# fpc.net
KiCad netlist of a schematic drawn in Altium Designer
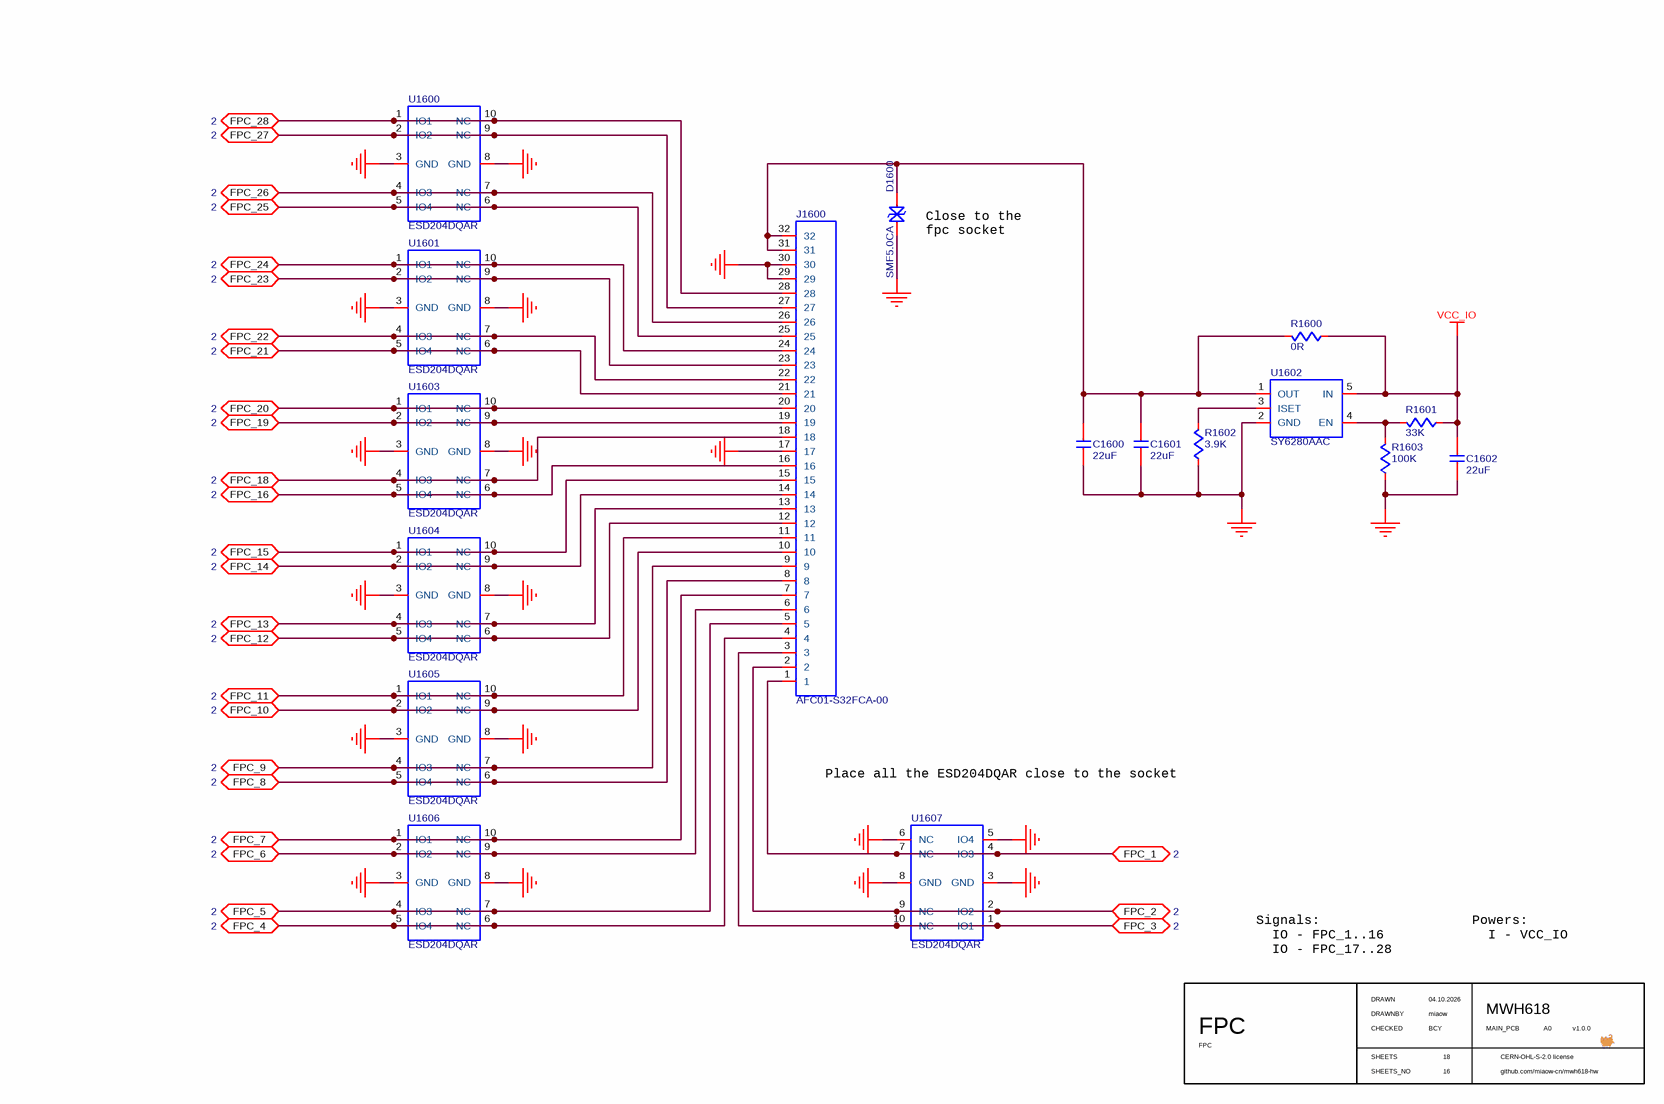
[diagram p0: fpc.schdoc]

(export (version "E")
  (design (tool "Eeschema 10.0.6"))
  (components
    (comp (ref "C1600")
      (value "22uF")
      (footprint "mw:C0603")
      (fields (field (name "VOLTAGE") "10V") (field (name "Comment") "C-NOMO"))
      (libsource (lib "mw") (part "C-NOMO"))
    )
    (comp (ref "C1601")
      (value "22uF")
      (footprint "mw:C0603")
      (fields (field (name "VOLTAGE") "10V") (field (name "Comment") "C-NOMO"))
      (libsource (lib "mw") (part "C-NOMO"))
    )
    (comp (ref "C1602")
      (value "22uF")
      (footprint "mw:C0603")
      (fields (field (name "VOLTAGE") "10V") (field (name "Comment") "C-NOMO"))
      (libsource (lib "mw") (part "C-NOMO"))
    )
    (comp (ref "D1600")
      (value "SMF5.0CA")
      (footprint "mw:SMF5.0CA")
      (description "TVS/ESD")
      (libsource (lib "mw") (part "SMF5.0CA"))
    )
    (comp (ref "J1600")
      (value "AFC01-S32FCA-00")
      (footprint "mw:AFC01-S32FCA-00")
      (description "FPC - flip, 32p, 0.5mm")
      (libsource (lib "mw") (part "AFC01-S32FCA-00"))
    )
    (comp (ref "R1600")
      (value "0R")
      (footprint "mw:R1206")
      (fields (field (name "Comment") "R"))
      (libsource (lib "mw") (part "R"))
    )
    (comp (ref "R1601")
      (value "33K")
      (footprint "mw:R0402")
      (fields (field (name "Comment") "R"))
      (libsource (lib "mw") (part "R"))
    )
    (comp (ref "R1602")
      (value "3.9K")
      (footprint "mw:R0402")
      (fields (field (name "Comment") "R"))
      (libsource (lib "mw") (part "R"))
    )
    (comp (ref "R1603")
      (value "100K")
      (footprint "mw:R0402")
      (fields (field (name "Comment") "R"))
      (libsource (lib "mw") (part "R"))
    )
    (comp (ref "U1600")
      (value "ESD204DQAR")
      (footprint "mw:ESD204DQAR")
      (description "TVS/ESD - 4 ch, 3.6V, 5V, 0.55pF@1MHz, 30KV")
      (libsource (lib "mw") (part "ESD204DQAR"))
    )
    (comp (ref "U1601")
      (value "ESD204DQAR")
      (footprint "mw:ESD204DQAR")
      (description "TVS/ESD - 4 ch, 3.6V, 5V, 0.55pF@1MHz, 30KV")
      (libsource (lib "mw") (part "ESD204DQAR"))
    )
    (comp (ref "U1602")
      (value "SY6280AAC")
      (footprint "mw:SY6280AAC")
      (description "PWR SWITCH")
      (libsource (lib "mw") (part "SY6280AAC"))
    )
    (comp (ref "U1603")
      (value "ESD204DQAR")
      (footprint "mw:ESD204DQAR")
      (description "TVS/ESD - 4 ch, 3.6V, 5V, 0.55pF@1MHz, 30KV")
      (libsource (lib "mw") (part "ESD204DQAR"))
    )
    (comp (ref "U1604")
      (value "ESD204DQAR")
      (footprint "mw:ESD204DQAR")
      (description "TVS/ESD - 4 ch, 3.6V, 5V, 0.55pF@1MHz, 30KV")
      (libsource (lib "mw") (part "ESD204DQAR"))
    )
    (comp (ref "U1605")
      (value "ESD204DQAR")
      (footprint "mw:ESD204DQAR")
      (description "TVS/ESD - 4 ch, 3.6V, 5V, 0.55pF@1MHz, 30KV")
      (libsource (lib "mw") (part "ESD204DQAR"))
    )
    (comp (ref "U1606")
      (value "ESD204DQAR")
      (footprint "mw:ESD204DQAR")
      (description "TVS/ESD - 4 ch, 3.6V, 5V, 0.55pF@1MHz, 30KV")
      (libsource (lib "mw") (part "ESD204DQAR"))
    )
    (comp (ref "U1607")
      (value "ESD204DQAR")
      (footprint "mw:ESD204DQAR")
      (description "TVS/ESD - 4 ch, 3.6V, 5V, 0.55pF@1MHz, 30KV")
      (libsource (lib "") (part "ESD204DQAR_1"))
    )
  )
  (nets
    (net (code "1") (name "/FPC_1") (class "Default")
      (node (ref "J1600") (pin "1") (pinfunction "1_1") (pintype "passive"))
      (node (ref "U1607") (pin "4") (pinfunction "IO3_4") (pintype "passive"))
      (node (ref "U1607") (pin "7") (pinfunction "NC_7") (pintype "passive"))
    )
    (net (code "2") (name "/FPC_2") (class "Default")
      (node (ref "J1600") (pin "2") (pinfunction "2_2") (pintype "passive"))
      (node (ref "U1607") (pin "2") (pinfunction "IO2_2") (pintype "passive"))
      (node (ref "U1607") (pin "9") (pinfunction "NC_9") (pintype "passive"))
    )
    (net (code "3") (name "/FPC_3") (class "Default")
      (node (ref "J1600") (pin "3") (pinfunction "3_3") (pintype "passive"))
      (node (ref "U1607") (pin "1") (pinfunction "IO1_1") (pintype "passive"))
      (node (ref "U1607") (pin "10") (pinfunction "NC_10") (pintype "passive"))
    )
    (net (code "4") (name "/FPC_4") (class "Default")
      (node (ref "J1600") (pin "4") (pinfunction "4_4") (pintype "passive"))
      (node (ref "U1606") (pin "5") (pinfunction "IO4_5") (pintype "passive"))
      (node (ref "U1606") (pin "6") (pinfunction "NC_6") (pintype "passive"))
    )
    (net (code "5") (name "/FPC_5") (class "Default")
      (node (ref "J1600") (pin "5") (pinfunction "5_5") (pintype "passive"))
      (node (ref "U1606") (pin "4") (pinfunction "IO3_4") (pintype "passive"))
      (node (ref "U1606") (pin "7") (pinfunction "NC_7") (pintype "passive"))
    )
    (net (code "6") (name "/FPC_6") (class "Default")
      (node (ref "J1600") (pin "6") (pinfunction "6_6") (pintype "passive"))
      (node (ref "U1606") (pin "2") (pinfunction "IO2_2") (pintype "passive"))
      (node (ref "U1606") (pin "9") (pinfunction "NC_9") (pintype "passive"))
    )
    (net (code "7") (name "/FPC_7") (class "Default")
      (node (ref "J1600") (pin "7") (pinfunction "7_7") (pintype "passive"))
      (node (ref "U1606") (pin "1") (pinfunction "IO1_1") (pintype "passive"))
      (node (ref "U1606") (pin "10") (pinfunction "NC_10") (pintype "passive"))
    )
    (net (code "8") (name "/FPC_8") (class "Default")
      (node (ref "J1600") (pin "8") (pinfunction "8_8") (pintype "passive"))
      (node (ref "U1605") (pin "5") (pinfunction "IO4_5") (pintype "passive"))
      (node (ref "U1605") (pin "6") (pinfunction "NC_6") (pintype "passive"))
    )
    (net (code "9") (name "/FPC_9") (class "Default")
      (node (ref "J1600") (pin "9") (pinfunction "9_9") (pintype "passive"))
      (node (ref "U1605") (pin "4") (pinfunction "IO3_4") (pintype "passive"))
      (node (ref "U1605") (pin "7") (pinfunction "NC_7") (pintype "passive"))
    )
    (net (code "10") (name "/FPC_10") (class "Default")
      (node (ref "J1600") (pin "10") (pinfunction "10_10") (pintype "passive"))
      (node (ref "U1605") (pin "2") (pinfunction "IO2_2") (pintype "passive"))
      (node (ref "U1605") (pin "9") (pinfunction "NC_9") (pintype "passive"))
    )
    (net (code "11") (name "/FPC_11") (class "Default")
      (node (ref "J1600") (pin "11") (pinfunction "11_11") (pintype "passive"))
      (node (ref "U1605") (pin "1") (pinfunction "IO1_1") (pintype "passive"))
      (node (ref "U1605") (pin "10") (pinfunction "NC_10") (pintype "passive"))
    )
    (net (code "12") (name "/FPC_12") (class "Default")
      (node (ref "J1600") (pin "12") (pinfunction "12_12") (pintype "passive"))
      (node (ref "U1604") (pin "5") (pinfunction "IO4_5") (pintype "passive"))
      (node (ref "U1604") (pin "6") (pinfunction "NC_6") (pintype "passive"))
    )
    (net (code "13") (name "/FPC_13") (class "Default")
      (node (ref "J1600") (pin "13") (pinfunction "13_13") (pintype "passive"))
      (node (ref "U1604") (pin "4") (pinfunction "IO3_4") (pintype "passive"))
      (node (ref "U1604") (pin "7") (pinfunction "NC_7") (pintype "passive"))
    )
    (net (code "14") (name "/FPC_14") (class "Default")
      (node (ref "J1600") (pin "14") (pinfunction "14_14") (pintype "passive"))
      (node (ref "U1604") (pin "2") (pinfunction "IO2_2") (pintype "passive"))
      (node (ref "U1604") (pin "9") (pinfunction "NC_9") (pintype "passive"))
    )
    (net (code "15") (name "/FPC_15") (class "Default")
      (node (ref "J1600") (pin "15") (pinfunction "15_15") (pintype "passive"))
      (node (ref "U1604") (pin "1") (pinfunction "IO1_1") (pintype "passive"))
      (node (ref "U1604") (pin "10") (pinfunction "NC_10") (pintype "passive"))
    )
    (net (code "16") (name "/FPC_16") (class "Default")
      (node (ref "J1600") (pin "16") (pinfunction "16_16") (pintype "passive"))
      (node (ref "U1603") (pin "5") (pinfunction "IO4_5") (pintype "passive"))
      (node (ref "U1603") (pin "6") (pinfunction "NC_6") (pintype "passive"))
    )
    (net (code "17") (name "/FPC_18") (class "Default")
      (node (ref "J1600") (pin "18") (pinfunction "18_18") (pintype "passive"))
      (node (ref "U1603") (pin "4") (pinfunction "IO3_4") (pintype "passive"))
      (node (ref "U1603") (pin "7") (pinfunction "NC_7") (pintype "passive"))
    )
    (net (code "18") (name "/FPC_19") (class "Default")
      (node (ref "J1600") (pin "19") (pinfunction "19_19") (pintype "passive"))
      (node (ref "U1603") (pin "2") (pinfunction "IO2_2") (pintype "passive"))
      (node (ref "U1603") (pin "9") (pinfunction "NC_9") (pintype "passive"))
    )
    (net (code "19") (name "/FPC_20") (class "Default")
      (node (ref "J1600") (pin "20") (pinfunction "20_20") (pintype "passive"))
      (node (ref "U1603") (pin "1") (pinfunction "IO1_1") (pintype "passive"))
      (node (ref "U1603") (pin "10") (pinfunction "NC_10") (pintype "passive"))
    )
    (net (code "20") (name "/FPC_21") (class "Default")
      (node (ref "J1600") (pin "21") (pinfunction "21_21") (pintype "passive"))
      (node (ref "U1601") (pin "5") (pinfunction "IO4_5") (pintype "passive"))
      (node (ref "U1601") (pin "6") (pinfunction "NC_6") (pintype "passive"))
    )
    (net (code "21") (name "/FPC_22") (class "Default")
      (node (ref "J1600") (pin "22") (pinfunction "22_22") (pintype "passive"))
      (node (ref "U1601") (pin "4") (pinfunction "IO3_4") (pintype "passive"))
      (node (ref "U1601") (pin "7") (pinfunction "NC_7") (pintype "passive"))
    )
    (net (code "22") (name "/FPC_23") (class "Default")
      (node (ref "J1600") (pin "23") (pinfunction "23_23") (pintype "passive"))
      (node (ref "U1601") (pin "2") (pinfunction "IO2_2") (pintype "passive"))
      (node (ref "U1601") (pin "9") (pinfunction "NC_9") (pintype "passive"))
    )
    (net (code "23") (name "/FPC_24") (class "Default")
      (node (ref "J1600") (pin "24") (pinfunction "24_24") (pintype "passive"))
      (node (ref "U1601") (pin "1") (pinfunction "IO1_1") (pintype "passive"))
      (node (ref "U1601") (pin "10") (pinfunction "NC_10") (pintype "passive"))
    )
    (net (code "24") (name "/FPC_25") (class "Default")
      (node (ref "J1600") (pin "25") (pinfunction "25_25") (pintype "passive"))
      (node (ref "U1600") (pin "5") (pinfunction "IO4_5") (pintype "passive"))
      (node (ref "U1600") (pin "6") (pinfunction "NC_6") (pintype "passive"))
    )
    (net (code "25") (name "/FPC_26") (class "Default")
      (node (ref "J1600") (pin "26") (pinfunction "26_26") (pintype "passive"))
      (node (ref "U1600") (pin "4") (pinfunction "IO3_4") (pintype "passive"))
      (node (ref "U1600") (pin "7") (pinfunction "NC_7") (pintype "passive"))
    )
    (net (code "26") (name "/FPC_27") (class "Default")
      (node (ref "J1600") (pin "27") (pinfunction "27_27") (pintype "passive"))
      (node (ref "U1600") (pin "2") (pinfunction "IO2_2") (pintype "passive"))
      (node (ref "U1600") (pin "9") (pinfunction "NC_9") (pintype "passive"))
    )
    (net (code "27") (name "/FPC_28") (class "Default")
      (node (ref "J1600") (pin "28") (pinfunction "28_28") (pintype "passive"))
      (node (ref "U1600") (pin "1") (pinfunction "IO1_1") (pintype "passive"))
      (node (ref "U1600") (pin "10") (pinfunction "NC_10") (pintype "passive"))
    )
    (net (code "28") (name "GND") (class "Default")
      (node (ref "C1600") (pin "2") (pinfunction "2_2") (pintype "passive"))
      (node (ref "C1601") (pin "2") (pinfunction "2_2") (pintype "passive"))
      (node (ref "C1602") (pin "2") (pinfunction "2_2") (pintype "passive"))
      (node (ref "D1600") (pin "1") (pinfunction "1_1") (pintype "passive"))
      (node (ref "J1600") (pin "17") (pinfunction "17_17") (pintype "passive"))
      (node (ref "J1600") (pin "29") (pinfunction "29_29") (pintype "passive"))
      (node (ref "J1600") (pin "30") (pinfunction "30_30") (pintype "passive"))
      (node (ref "R1602") (pin "2") (pinfunction "2_2") (pintype "passive"))
      (node (ref "R1603") (pin "2") (pinfunction "2_2") (pintype "passive"))
      (node (ref "U1600") (pin "3") (pinfunction "GND_3") (pintype "passive"))
      (node (ref "U1600") (pin "8") (pinfunction "GND_8") (pintype "passive"))
      (node (ref "U1601") (pin "3") (pinfunction "GND_3") (pintype "passive"))
      (node (ref "U1601") (pin "8") (pinfunction "GND_8") (pintype "passive"))
      (node (ref "U1602") (pin "2") (pinfunction "GND_2") (pintype "passive"))
      (node (ref "U1603") (pin "3") (pinfunction "GND_3") (pintype "passive"))
      (node (ref "U1603") (pin "8") (pinfunction "GND_8") (pintype "passive"))
      (node (ref "U1604") (pin "3") (pinfunction "GND_3") (pintype "passive"))
      (node (ref "U1604") (pin "8") (pinfunction "GND_8") (pintype "passive"))
      (node (ref "U1605") (pin "3") (pinfunction "GND_3") (pintype "passive"))
      (node (ref "U1605") (pin "8") (pinfunction "GND_8") (pintype "passive"))
      (node (ref "U1606") (pin "3") (pinfunction "GND_3") (pintype "passive"))
      (node (ref "U1606") (pin "8") (pinfunction "GND_8") (pintype "passive"))
      (node (ref "U1607") (pin "3") (pinfunction "GND_3") (pintype "passive"))
      (node (ref "U1607") (pin "5") (pinfunction "IO4_5") (pintype "passive"))
      (node (ref "U1607") (pin "6") (pinfunction "NC_6") (pintype "passive"))
      (node (ref "U1607") (pin "8") (pinfunction "GND_8") (pintype "passive"))
    )
    (net (code "29") (name "Net-(U1602-EN)") (class "Default")
      (node (ref "R1601") (pin "1") (pinfunction "1_1") (pintype "passive"))
      (node (ref "R1603") (pin "1") (pinfunction "1_1") (pintype "passive"))
      (node (ref "U1602") (pin "4") (pinfunction "EN_4") (pintype "passive"))
    )
    (net (code "30") (name "Net-(U1602-ISET)") (class "Default")
      (node (ref "R1602") (pin "1") (pinfunction "1_1") (pintype "passive"))
      (node (ref "U1602") (pin "3") (pinfunction "ISET_3") (pintype "passive"))
    )
    (net (code "31") (name "Net-(U1602-OUT)") (class "Default")
      (node (ref "C1600") (pin "1") (pinfunction "1_1") (pintype "passive"))
      (node (ref "C1601") (pin "1") (pinfunction "1_1") (pintype "passive"))
      (node (ref "D1600") (pin "2") (pinfunction "2_2") (pintype "passive"))
      (node (ref "J1600") (pin "31") (pinfunction "31_31") (pintype "passive"))
      (node (ref "J1600") (pin "32") (pinfunction "32_32") (pintype "passive"))
      (node (ref "R1600") (pin "1") (pinfunction "1_1") (pintype "passive"))
      (node (ref "U1602") (pin "1") (pinfunction "OUT_1") (pintype "passive"))
    )
    (net (code "32") (name "VCC_IO") (class "Default")
      (node (ref "C1602") (pin "1") (pinfunction "1_1") (pintype "passive"))
      (node (ref "R1600") (pin "2") (pinfunction "2_2") (pintype "passive"))
      (node (ref "R1601") (pin "2") (pinfunction "2_2") (pintype "passive"))
      (node (ref "U1602") (pin "5") (pinfunction "IN_5") (pintype "passive"))
    )
  )
)
